# RingBoard.net
KiCad netlist of a schematic drawn in EAGLE
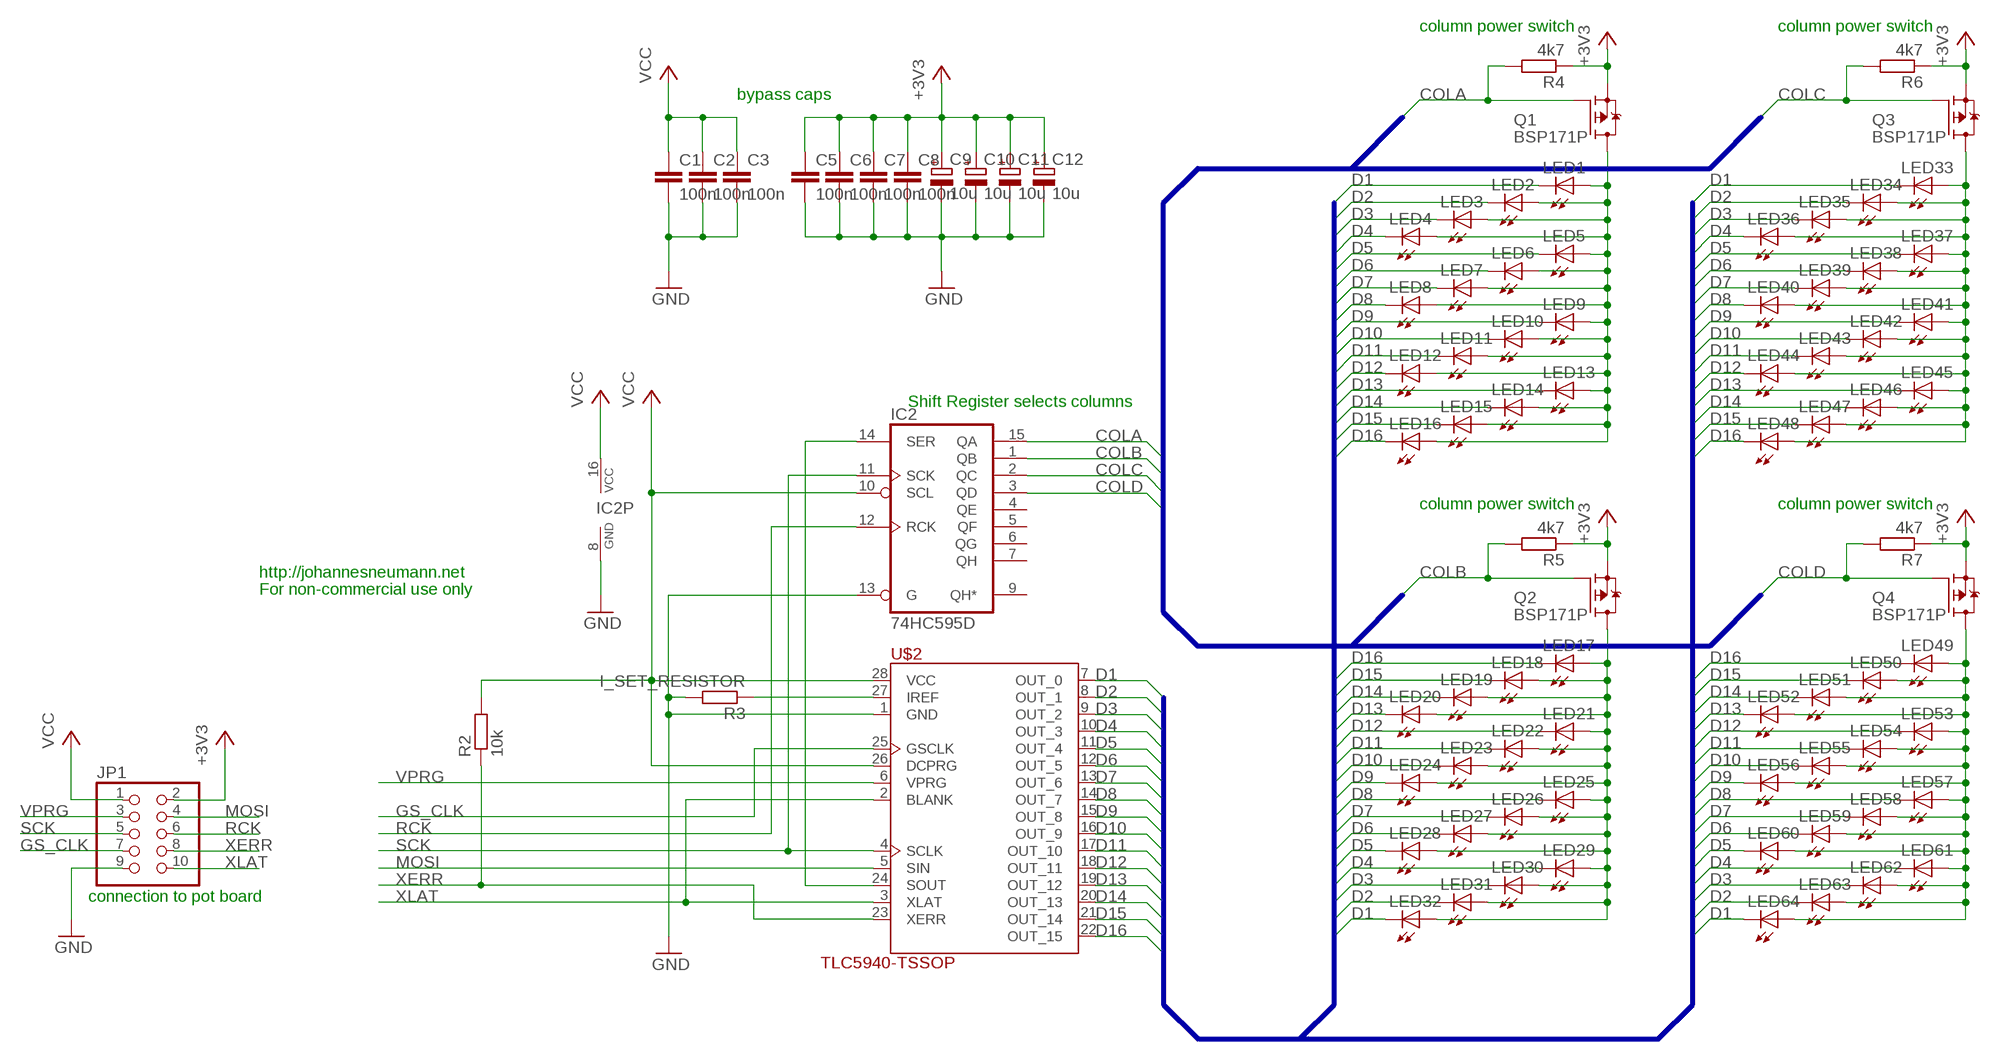
[diagram p0: schematic, sheet 1]

(export (version "E")
  (design (tool "Eeschema 10.0.6"))
  (components
    (comp (ref "C1")
      (value "100n")
      (footprint "eagle-import:C0603")
      (libsource (lib "eagle-import") (part "C-EUC0603"))
    )
    (comp (ref "C2")
      (value "100n")
      (footprint "eagle-import:C0603")
      (libsource (lib "eagle-import") (part "C-EUC0603"))
    )
    (comp (ref "C3")
      (value "100n")
      (footprint "eagle-import:C0603")
      (libsource (lib "eagle-import") (part "C-EUC0603"))
    )
    (comp (ref "C5")
      (value "100n")
      (footprint "eagle-import:C0603")
      (libsource (lib "eagle-import") (part "C-EUC0603"))
    )
    (comp (ref "C6")
      (value "100n")
      (footprint "eagle-import:C0603")
      (libsource (lib "eagle-import") (part "C-EUC0603"))
    )
    (comp (ref "C7")
      (value "100n")
      (footprint "eagle-import:C0603")
      (libsource (lib "eagle-import") (part "C-EUC0603"))
    )
    (comp (ref "C8")
      (value "100n")
      (footprint "eagle-import:C0603")
      (libsource (lib "eagle-import") (part "C-EUC0603"))
    )
    (comp (ref "C9")
      (value "10u")
      (footprint "eagle-import:153CLV-0605")
      (libsource (lib "eagle-import") (part "CPOL-EU153CLV-0605"))
    )
    (comp (ref "C10")
      (value "10u")
      (footprint "eagle-import:153CLV-0605")
      (libsource (lib "eagle-import") (part "CPOL-EU153CLV-0605"))
    )
    (comp (ref "C11")
      (value "10u")
      (footprint "eagle-import:153CLV-0605")
      (libsource (lib "eagle-import") (part "CPOL-EU153CLV-0605"))
    )
    (comp (ref "C12")
      (value "10u")
      (footprint "eagle-import:153CLV-0605")
      (libsource (lib "eagle-import") (part "CPOL-EU153CLV-0605"))
    )
    (comp (ref "IC2")
      (value "74HC595D")
      (footprint "eagle-import:SO16")
      (libsource (lib "eagle-import") (part "74595DHC"))
    )
    (comp (ref "JP1")
      (value "PINHD-2X5_2.54-SMD")
      (footprint "eagle-import:2X05SMD")
      (libsource (lib "eagle-import") (part "PINHD-2X5_2.54-SMD"))
    )
    (comp (ref "LED1")
      (value "LEDCHIP-LED0805")
      (footprint "eagle-import:CHIP-LED0805")
      (libsource (lib "eagle-import") (part "LEDCHIP-LED0805"))
    )
    (comp (ref "LED2")
      (value "LEDCHIP-LED0805")
      (footprint "eagle-import:CHIP-LED0805")
      (libsource (lib "eagle-import") (part "LEDCHIP-LED0805"))
    )
    (comp (ref "LED3")
      (value "LEDCHIP-LED0805")
      (footprint "eagle-import:CHIP-LED0805")
      (libsource (lib "eagle-import") (part "LEDCHIP-LED0805"))
    )
    (comp (ref "LED4")
      (value "LEDCHIP-LED0805")
      (footprint "eagle-import:CHIP-LED0805")
      (libsource (lib "eagle-import") (part "LEDCHIP-LED0805"))
    )
    (comp (ref "LED5")
      (value "LEDCHIP-LED0805")
      (footprint "eagle-import:CHIP-LED0805")
      (libsource (lib "eagle-import") (part "LEDCHIP-LED0805"))
    )
    (comp (ref "LED6")
      (value "LEDCHIP-LED0805")
      (footprint "eagle-import:CHIP-LED0805")
      (libsource (lib "eagle-import") (part "LEDCHIP-LED0805"))
    )
    (comp (ref "LED7")
      (value "LEDCHIP-LED0805")
      (footprint "eagle-import:CHIP-LED0805")
      (libsource (lib "eagle-import") (part "LEDCHIP-LED0805"))
    )
    (comp (ref "LED8")
      (value "LEDCHIP-LED0805")
      (footprint "eagle-import:CHIP-LED0805")
      (libsource (lib "eagle-import") (part "LEDCHIP-LED0805"))
    )
    (comp (ref "LED9")
      (value "LEDCHIP-LED0805")
      (footprint "eagle-import:CHIP-LED0805")
      (libsource (lib "eagle-import") (part "LEDCHIP-LED0805"))
    )
    (comp (ref "LED10")
      (value "LEDCHIP-LED0805")
      (footprint "eagle-import:CHIP-LED0805")
      (libsource (lib "eagle-import") (part "LEDCHIP-LED0805"))
    )
    (comp (ref "LED11")
      (value "LEDCHIP-LED0805")
      (footprint "eagle-import:CHIP-LED0805")
      (libsource (lib "eagle-import") (part "LEDCHIP-LED0805"))
    )
    (comp (ref "LED12")
      (value "LEDCHIP-LED0805")
      (footprint "eagle-import:CHIP-LED0805")
      (libsource (lib "eagle-import") (part "LEDCHIP-LED0805"))
    )
    (comp (ref "LED13")
      (value "LEDCHIP-LED0805")
      (footprint "eagle-import:CHIP-LED0805")
      (libsource (lib "eagle-import") (part "LEDCHIP-LED0805"))
    )
    (comp (ref "LED14")
      (value "LEDCHIP-LED0805")
      (footprint "eagle-import:CHIP-LED0805")
      (libsource (lib "eagle-import") (part "LEDCHIP-LED0805"))
    )
    (comp (ref "LED15")
      (value "LEDCHIP-LED0805")
      (footprint "eagle-import:CHIP-LED0805")
      (libsource (lib "eagle-import") (part "LEDCHIP-LED0805"))
    )
    (comp (ref "LED16")
      (value "LEDCHIP-LED0805")
      (footprint "eagle-import:CHIP-LED0805")
      (libsource (lib "eagle-import") (part "LEDCHIP-LED0805"))
    )
    (comp (ref "LED17")
      (value "LEDCHIP-LED0805")
      (footprint "eagle-import:CHIP-LED0805")
      (libsource (lib "eagle-import") (part "LEDCHIP-LED0805"))
    )
    (comp (ref "LED18")
      (value "LEDCHIP-LED0805")
      (footprint "eagle-import:CHIP-LED0805")
      (libsource (lib "eagle-import") (part "LEDCHIP-LED0805"))
    )
    (comp (ref "LED19")
      (value "LEDCHIP-LED0805")
      (footprint "eagle-import:CHIP-LED0805")
      (libsource (lib "eagle-import") (part "LEDCHIP-LED0805"))
    )
    (comp (ref "LED20")
      (value "LEDCHIP-LED0805")
      (footprint "eagle-import:CHIP-LED0805")
      (libsource (lib "eagle-import") (part "LEDCHIP-LED0805"))
    )
    (comp (ref "LED21")
      (value "LEDCHIP-LED0805")
      (footprint "eagle-import:CHIP-LED0805")
      (libsource (lib "eagle-import") (part "LEDCHIP-LED0805"))
    )
    (comp (ref "LED22")
      (value "LEDCHIP-LED0805")
      (footprint "eagle-import:CHIP-LED0805")
      (libsource (lib "eagle-import") (part "LEDCHIP-LED0805"))
    )
    (comp (ref "LED23")
      (value "LEDCHIP-LED0805")
      (footprint "eagle-import:CHIP-LED0805")
      (libsource (lib "eagle-import") (part "LEDCHIP-LED0805"))
    )
    (comp (ref "LED24")
      (value "LEDCHIP-LED0805")
      (footprint "eagle-import:CHIP-LED0805")
      (libsource (lib "eagle-import") (part "LEDCHIP-LED0805"))
    )
    (comp (ref "LED25")
      (value "LEDCHIP-LED0805")
      (footprint "eagle-import:CHIP-LED0805")
      (libsource (lib "eagle-import") (part "LEDCHIP-LED0805"))
    )
    (comp (ref "LED26")
      (value "LEDCHIP-LED0805")
      (footprint "eagle-import:CHIP-LED0805")
      (libsource (lib "eagle-import") (part "LEDCHIP-LED0805"))
    )
    (comp (ref "LED27")
      (value "LEDCHIP-LED0805")
      (footprint "eagle-import:CHIP-LED0805")
      (libsource (lib "eagle-import") (part "LEDCHIP-LED0805"))
    )
    (comp (ref "LED28")
      (value "LEDCHIP-LED0805")
      (footprint "eagle-import:CHIP-LED0805")
      (libsource (lib "eagle-import") (part "LEDCHIP-LED0805"))
    )
    (comp (ref "LED29")
      (value "LEDCHIP-LED0805")
      (footprint "eagle-import:CHIP-LED0805")
      (libsource (lib "eagle-import") (part "LEDCHIP-LED0805"))
    )
    (comp (ref "LED30")
      (value "LEDCHIP-LED0805")
      (footprint "eagle-import:CHIP-LED0805")
      (libsource (lib "eagle-import") (part "LEDCHIP-LED0805"))
    )
    (comp (ref "LED31")
      (value "LEDCHIP-LED0805")
      (footprint "eagle-import:CHIP-LED0805")
      (libsource (lib "eagle-import") (part "LEDCHIP-LED0805"))
    )
    (comp (ref "LED32")
      (value "LEDCHIP-LED0805")
      (footprint "eagle-import:CHIP-LED0805")
      (libsource (lib "eagle-import") (part "LEDCHIP-LED0805"))
    )
    (comp (ref "LED33")
      (value "LEDCHIP-LED0805")
      (footprint "eagle-import:CHIP-LED0805")
      (libsource (lib "eagle-import") (part "LEDCHIP-LED0805"))
    )
    (comp (ref "LED34")
      (value "LEDCHIP-LED0805")
      (footprint "eagle-import:CHIP-LED0805")
      (libsource (lib "eagle-import") (part "LEDCHIP-LED0805"))
    )
    (comp (ref "LED35")
      (value "LEDCHIP-LED0805")
      (footprint "eagle-import:CHIP-LED0805")
      (libsource (lib "eagle-import") (part "LEDCHIP-LED0805"))
    )
    (comp (ref "LED36")
      (value "LEDCHIP-LED0805")
      (footprint "eagle-import:CHIP-LED0805")
      (libsource (lib "eagle-import") (part "LEDCHIP-LED0805"))
    )
    (comp (ref "LED37")
      (value "LEDCHIP-LED0805")
      (footprint "eagle-import:CHIP-LED0805")
      (libsource (lib "eagle-import") (part "LEDCHIP-LED0805"))
    )
    (comp (ref "LED38")
      (value "LEDCHIP-LED0805")
      (footprint "eagle-import:CHIP-LED0805")
      (libsource (lib "eagle-import") (part "LEDCHIP-LED0805"))
    )
    (comp (ref "LED39")
      (value "LEDCHIP-LED0805")
      (footprint "eagle-import:CHIP-LED0805")
      (libsource (lib "eagle-import") (part "LEDCHIP-LED0805"))
    )
    (comp (ref "LED40")
      (value "LEDCHIP-LED0805")
      (footprint "eagle-import:CHIP-LED0805")
      (libsource (lib "eagle-import") (part "LEDCHIP-LED0805"))
    )
    (comp (ref "LED41")
      (value "LEDCHIP-LED0805")
      (footprint "eagle-import:CHIP-LED0805")
      (libsource (lib "eagle-import") (part "LEDCHIP-LED0805"))
    )
    (comp (ref "LED42")
      (value "LEDCHIP-LED0805")
      (footprint "eagle-import:CHIP-LED0805")
      (libsource (lib "eagle-import") (part "LEDCHIP-LED0805"))
    )
    (comp (ref "LED43")
      (value "LEDCHIP-LED0805")
      (footprint "eagle-import:CHIP-LED0805")
      (libsource (lib "eagle-import") (part "LEDCHIP-LED0805"))
    )
    (comp (ref "LED44")
      (value "LEDCHIP-LED0805")
      (footprint "eagle-import:CHIP-LED0805")
      (libsource (lib "eagle-import") (part "LEDCHIP-LED0805"))
    )
    (comp (ref "LED45")
      (value "LEDCHIP-LED0805")
      (footprint "eagle-import:CHIP-LED0805")
      (libsource (lib "eagle-import") (part "LEDCHIP-LED0805"))
    )
    (comp (ref "LED46")
      (value "LEDCHIP-LED0805")
      (footprint "eagle-import:CHIP-LED0805")
      (libsource (lib "eagle-import") (part "LEDCHIP-LED0805"))
    )
    (comp (ref "LED47")
      (value "LEDCHIP-LED0805")
      (footprint "eagle-import:CHIP-LED0805")
      (libsource (lib "eagle-import") (part "LEDCHIP-LED0805"))
    )
    (comp (ref "LED48")
      (value "LEDCHIP-LED0805")
      (footprint "eagle-import:CHIP-LED0805")
      (libsource (lib "eagle-import") (part "LEDCHIP-LED0805"))
    )
    (comp (ref "LED49")
      (value "LEDCHIP-LED0805")
      (footprint "eagle-import:CHIP-LED0805")
      (libsource (lib "eagle-import") (part "LEDCHIP-LED0805"))
    )
    (comp (ref "LED50")
      (value "LEDCHIP-LED0805")
      (footprint "eagle-import:CHIP-LED0805")
      (libsource (lib "eagle-import") (part "LEDCHIP-LED0805"))
    )
    (comp (ref "LED51")
      (value "LEDCHIP-LED0805")
      (footprint "eagle-import:CHIP-LED0805")
      (libsource (lib "eagle-import") (part "LEDCHIP-LED0805"))
    )
    (comp (ref "LED52")
      (value "LEDCHIP-LED0805")
      (footprint "eagle-import:CHIP-LED0805")
      (libsource (lib "eagle-import") (part "LEDCHIP-LED0805"))
    )
    (comp (ref "LED53")
      (value "LEDCHIP-LED0805")
      (footprint "eagle-import:CHIP-LED0805")
      (libsource (lib "eagle-import") (part "LEDCHIP-LED0805"))
    )
    (comp (ref "LED54")
      (value "LEDCHIP-LED0805")
      (footprint "eagle-import:CHIP-LED0805")
      (libsource (lib "eagle-import") (part "LEDCHIP-LED0805"))
    )
    (comp (ref "LED55")
      (value "LEDCHIP-LED0805")
      (footprint "eagle-import:CHIP-LED0805")
      (libsource (lib "eagle-import") (part "LEDCHIP-LED0805"))
    )
    (comp (ref "LED56")
      (value "LEDCHIP-LED0805")
      (footprint "eagle-import:CHIP-LED0805")
      (libsource (lib "eagle-import") (part "LEDCHIP-LED0805"))
    )
    (comp (ref "LED57")
      (value "LEDCHIP-LED0805")
      (footprint "eagle-import:CHIP-LED0805")
      (libsource (lib "eagle-import") (part "LEDCHIP-LED0805"))
    )
    (comp (ref "LED58")
      (value "LEDCHIP-LED0805")
      (footprint "eagle-import:CHIP-LED0805")
      (libsource (lib "eagle-import") (part "LEDCHIP-LED0805"))
    )
    (comp (ref "LED59")
      (value "LEDCHIP-LED0805")
      (footprint "eagle-import:CHIP-LED0805")
      (libsource (lib "eagle-import") (part "LEDCHIP-LED0805"))
    )
    (comp (ref "LED60")
      (value "LEDCHIP-LED0805")
      (footprint "eagle-import:CHIP-LED0805")
      (libsource (lib "eagle-import") (part "LEDCHIP-LED0805"))
    )
    (comp (ref "LED61")
      (value "LEDCHIP-LED0805")
      (footprint "eagle-import:CHIP-LED0805")
      (libsource (lib "eagle-import") (part "LEDCHIP-LED0805"))
    )
    (comp (ref "LED62")
      (value "LEDCHIP-LED0805")
      (footprint "eagle-import:CHIP-LED0805")
      (libsource (lib "eagle-import") (part "LEDCHIP-LED0805"))
    )
    (comp (ref "LED63")
      (value "LEDCHIP-LED0805")
      (footprint "eagle-import:CHIP-LED0805")
      (libsource (lib "eagle-import") (part "LEDCHIP-LED0805"))
    )
    (comp (ref "LED64")
      (value "LEDCHIP-LED0805")
      (footprint "eagle-import:CHIP-LED0805")
      (libsource (lib "eagle-import") (part "LEDCHIP-LED0805"))
    )
    (comp (ref "Q1")
      (value "BSP171P")
      (footprint "eagle-import:SOT223")
      (libsource (lib "eagle-import") (part "BSP170P"))
    )
    (comp (ref "Q2")
      (value "BSP171P")
      (footprint "eagle-import:SOT223")
      (libsource (lib "eagle-import") (part "BSP170P"))
    )
    (comp (ref "Q3")
      (value "BSP171P")
      (footprint "eagle-import:SOT223")
      (libsource (lib "eagle-import") (part "BSP170P"))
    )
    (comp (ref "Q4")
      (value "BSP171P")
      (footprint "eagle-import:SOT223")
      (libsource (lib "eagle-import") (part "BSP170P"))
    )
    (comp (ref "R2")
      (value "10k")
      (footprint "eagle-import:R0603")
      (libsource (lib "eagle-import") (part "R-EU_R0603"))
    )
    (comp (ref "R3")
      (value "I_SET_RESISTOR")
      (footprint "eagle-import:M1406")
      (libsource (lib "eagle-import") (part "R-EU_M1406"))
    )
    (comp (ref "R4")
      (value "4k7")
      (footprint "eagle-import:R0603")
      (libsource (lib "eagle-import") (part "R-EU_R0603"))
    )
    (comp (ref "R5")
      (value "4k7")
      (footprint "eagle-import:R0603")
      (libsource (lib "eagle-import") (part "R-EU_R0603"))
    )
    (comp (ref "R6")
      (value "4k7")
      (footprint "eagle-import:R0603")
      (libsource (lib "eagle-import") (part "R-EU_R0603"))
    )
    (comp (ref "R7")
      (value "4k7")
      (footprint "eagle-import:R0603")
      (libsource (lib "eagle-import") (part "R-EU_R0603"))
    )
    (comp (ref "U$2")
      (value "TLC5940-TSSOP")
      (footprint "eagle-import:HTSSOP-28")
      (libsource (lib "eagle-import") (part "TLC5940-TSSOP"))
    )
  )
  (nets
    (net (code "1") (name "+3V3") (class "Default")
      (node (ref "C10") (pin "+") (pinfunction "+_+") (pintype "passive"))
      (node (ref "C11") (pin "+") (pinfunction "+_+") (pintype "passive"))
      (node (ref "C12") (pin "+") (pinfunction "+_+") (pintype "passive"))
      (node (ref "C5") (pin "1") (pinfunction "1_1") (pintype "passive"))
      (node (ref "C6") (pin "1") (pinfunction "1_1") (pintype "passive"))
      (node (ref "C7") (pin "1") (pinfunction "1_1") (pintype "passive"))
      (node (ref "C8") (pin "1") (pinfunction "1_1") (pintype "passive"))
      (node (ref "C9") (pin "+") (pinfunction "+_+") (pintype "passive"))
      (node (ref "JP1") (pin "2") (pinfunction "2_2") (pintype "passive"))
      (node (ref "Q1") (pin "3") (pinfunction "S_3") (pintype "passive"))
      (node (ref "Q2") (pin "3") (pinfunction "S_3") (pintype "passive"))
      (node (ref "Q3") (pin "3") (pinfunction "S_3") (pintype "passive"))
      (node (ref "Q4") (pin "3") (pinfunction "S_3") (pintype "passive"))
      (node (ref "R4") (pin "1") (pinfunction "1_1") (pintype "passive"))
      (node (ref "R5") (pin "1") (pinfunction "1_1") (pintype "passive"))
      (node (ref "R6") (pin "1") (pinfunction "1_1") (pintype "passive"))
      (node (ref "R7") (pin "1") (pinfunction "1_1") (pintype "passive"))
    )
    (net (code "2") (name "/COLA") (class "Default")
      (node (ref "IC2") (pin "15") (pinfunction "QA_15") (pintype "tri_state"))
      (node (ref "Q1") (pin "1") (pinfunction "G_1") (pintype "passive"))
      (node (ref "R4") (pin "2") (pinfunction "2_2") (pintype "passive"))
    )
    (net (code "3") (name "/COLB") (class "Default")
      (node (ref "IC2") (pin "1") (pinfunction "QB_1") (pintype "tri_state"))
      (node (ref "Q2") (pin "1") (pinfunction "G_1") (pintype "passive"))
      (node (ref "R5") (pin "2") (pinfunction "2_2") (pintype "passive"))
    )
    (net (code "4") (name "/COLC") (class "Default")
      (node (ref "IC2") (pin "2") (pinfunction "QC_2") (pintype "tri_state"))
      (node (ref "Q3") (pin "1") (pinfunction "G_1") (pintype "passive"))
      (node (ref "R6") (pin "2") (pinfunction "2_2") (pintype "passive"))
    )
    (net (code "5") (name "/COLD") (class "Default")
      (node (ref "IC2") (pin "3") (pinfunction "QD_3") (pintype "tri_state"))
      (node (ref "Q4") (pin "1") (pinfunction "G_1") (pintype "passive"))
      (node (ref "R7") (pin "2") (pinfunction "2_2") (pintype "passive"))
    )
    (net (code "6") (name "/D1") (class "Default")
      (node (ref "LED1") (pin "C") (pinfunction "C_C") (pintype "passive"))
      (node (ref "LED32") (pin "C") (pinfunction "C_C") (pintype "passive"))
      (node (ref "LED33") (pin "C") (pinfunction "C_C") (pintype "passive"))
      (node (ref "LED64") (pin "C") (pinfunction "C_C") (pintype "passive"))
      (node (ref "U$2") (pin "7") (pinfunction "OUT_0_7") (pintype "output"))
    )
    (net (code "7") (name "/D2") (class "Default")
      (node (ref "LED2") (pin "C") (pinfunction "C_C") (pintype "passive"))
      (node (ref "LED31") (pin "C") (pinfunction "C_C") (pintype "passive"))
      (node (ref "LED34") (pin "C") (pinfunction "C_C") (pintype "passive"))
      (node (ref "LED63") (pin "C") (pinfunction "C_C") (pintype "passive"))
      (node (ref "U$2") (pin "8") (pinfunction "OUT_1_8") (pintype "output"))
    )
    (net (code "8") (name "/D3") (class "Default")
      (node (ref "LED3") (pin "C") (pinfunction "C_C") (pintype "passive"))
      (node (ref "LED30") (pin "C") (pinfunction "C_C") (pintype "passive"))
      (node (ref "LED35") (pin "C") (pinfunction "C_C") (pintype "passive"))
      (node (ref "LED62") (pin "C") (pinfunction "C_C") (pintype "passive"))
      (node (ref "U$2") (pin "9") (pinfunction "OUT_2_9") (pintype "output"))
    )
    (net (code "9") (name "/D4") (class "Default")
      (node (ref "LED29") (pin "C") (pinfunction "C_C") (pintype "passive"))
      (node (ref "LED36") (pin "C") (pinfunction "C_C") (pintype "passive"))
      (node (ref "LED4") (pin "C") (pinfunction "C_C") (pintype "passive"))
      (node (ref "LED61") (pin "C") (pinfunction "C_C") (pintype "passive"))
      (node (ref "U$2") (pin "10") (pinfunction "OUT_3_10") (pintype "output"))
    )
    (net (code "10") (name "/D5") (class "Default")
      (node (ref "LED28") (pin "C") (pinfunction "C_C") (pintype "passive"))
      (node (ref "LED37") (pin "C") (pinfunction "C_C") (pintype "passive"))
      (node (ref "LED5") (pin "C") (pinfunction "C_C") (pintype "passive"))
      (node (ref "LED60") (pin "C") (pinfunction "C_C") (pintype "passive"))
      (node (ref "U$2") (pin "11") (pinfunction "OUT_4_11") (pintype "output"))
    )
    (net (code "11") (name "/D6") (class "Default")
      (node (ref "LED27") (pin "C") (pinfunction "C_C") (pintype "passive"))
      (node (ref "LED38") (pin "C") (pinfunction "C_C") (pintype "passive"))
      (node (ref "LED59") (pin "C") (pinfunction "C_C") (pintype "passive"))
      (node (ref "LED6") (pin "C") (pinfunction "C_C") (pintype "passive"))
      (node (ref "U$2") (pin "12") (pinfunction "OUT_5_12") (pintype "output"))
    )
    (net (code "12") (name "/D7") (class "Default")
      (node (ref "LED26") (pin "C") (pinfunction "C_C") (pintype "passive"))
      (node (ref "LED39") (pin "C") (pinfunction "C_C") (pintype "passive"))
      (node (ref "LED58") (pin "C") (pinfunction "C_C") (pintype "passive"))
      (node (ref "LED7") (pin "C") (pinfunction "C_C") (pintype "passive"))
      (node (ref "U$2") (pin "13") (pinfunction "OUT_6_13") (pintype "output"))
    )
    (net (code "13") (name "/D8") (class "Default")
      (node (ref "LED25") (pin "C") (pinfunction "C_C") (pintype "passive"))
      (node (ref "LED40") (pin "C") (pinfunction "C_C") (pintype "passive"))
      (node (ref "LED57") (pin "C") (pinfunction "C_C") (pintype "passive"))
      (node (ref "LED8") (pin "C") (pinfunction "C_C") (pintype "passive"))
      (node (ref "U$2") (pin "14") (pinfunction "OUT_7_14") (pintype "output"))
    )
    (net (code "14") (name "/D9") (class "Default")
      (node (ref "LED24") (pin "C") (pinfunction "C_C") (pintype "passive"))
      (node (ref "LED41") (pin "C") (pinfunction "C_C") (pintype "passive"))
      (node (ref "LED56") (pin "C") (pinfunction "C_C") (pintype "passive"))
      (node (ref "LED9") (pin "C") (pinfunction "C_C") (pintype "passive"))
      (node (ref "U$2") (pin "15") (pinfunction "OUT_8_15") (pintype "output"))
    )
    (net (code "15") (name "/D10") (class "Default")
      (node (ref "LED10") (pin "C") (pinfunction "C_C") (pintype "passive"))
      (node (ref "LED23") (pin "C") (pinfunction "C_C") (pintype "passive"))
      (node (ref "LED42") (pin "C") (pinfunction "C_C") (pintype "passive"))
      (node (ref "LED55") (pin "C") (pinfunction "C_C") (pintype "passive"))
      (node (ref "U$2") (pin "16") (pinfunction "OUT_9_16") (pintype "output"))
    )
    (net (code "16") (name "/D11") (class "Default")
      (node (ref "LED11") (pin "C") (pinfunction "C_C") (pintype "passive"))
      (node (ref "LED22") (pin "C") (pinfunction "C_C") (pintype "passive"))
      (node (ref "LED43") (pin "C") (pinfunction "C_C") (pintype "passive"))
      (node (ref "LED54") (pin "C") (pinfunction "C_C") (pintype "passive"))
      (node (ref "U$2") (pin "17") (pinfunction "OUT_10_17") (pintype "output"))
    )
    (net (code "17") (name "/D12") (class "Default")
      (node (ref "LED12") (pin "C") (pinfunction "C_C") (pintype "passive"))
      (node (ref "LED21") (pin "C") (pinfunction "C_C") (pintype "passive"))
      (node (ref "LED44") (pin "C") (pinfunction "C_C") (pintype "passive"))
      (node (ref "LED53") (pin "C") (pinfunction "C_C") (pintype "passive"))
      (node (ref "U$2") (pin "18") (pinfunction "OUT_11_18") (pintype "output"))
    )
    (net (code "18") (name "/D13") (class "Default")
      (node (ref "LED13") (pin "C") (pinfunction "C_C") (pintype "passive"))
      (node (ref "LED20") (pin "C") (pinfunction "C_C") (pintype "passive"))
      (node (ref "LED45") (pin "C") (pinfunction "C_C") (pintype "passive"))
      (node (ref "LED52") (pin "C") (pinfunction "C_C") (pintype "passive"))
      (node (ref "U$2") (pin "19") (pinfunction "OUT_12_19") (pintype "output"))
    )
    (net (code "19") (name "/D14") (class "Default")
      (node (ref "LED14") (pin "C") (pinfunction "C_C") (pintype "passive"))
      (node (ref "LED19") (pin "C") (pinfunction "C_C") (pintype "passive"))
      (node (ref "LED46") (pin "C") (pinfunction "C_C") (pintype "passive"))
      (node (ref "LED51") (pin "C") (pinfunction "C_C") (pintype "passive"))
      (node (ref "U$2") (pin "20") (pinfunction "OUT_13_20") (pintype "output"))
    )
    (net (code "20") (name "/D15") (class "Default")
      (node (ref "LED15") (pin "C") (pinfunction "C_C") (pintype "passive"))
      (node (ref "LED18") (pin "C") (pinfunction "C_C") (pintype "passive"))
      (node (ref "LED47") (pin "C") (pinfunction "C_C") (pintype "passive"))
      (node (ref "LED50") (pin "C") (pinfunction "C_C") (pintype "passive"))
      (node (ref "U$2") (pin "21") (pinfunction "OUT_14_21") (pintype "output"))
    )
    (net (code "21") (name "/D16") (class "Default")
      (node (ref "LED16") (pin "C") (pinfunction "C_C") (pintype "passive"))
      (node (ref "LED17") (pin "C") (pinfunction "C_C") (pintype "passive"))
      (node (ref "LED48") (pin "C") (pinfunction "C_C") (pintype "passive"))
      (node (ref "LED49") (pin "C") (pinfunction "C_C") (pintype "passive"))
      (node (ref "U$2") (pin "22") (pinfunction "OUT_15_22") (pintype "output"))
    )
    (net (code "22") (name "/GS_CLK") (class "Default")
      (node (ref "JP1") (pin "7") (pinfunction "7_7") (pintype "passive"))
      (node (ref "U$2") (pin "25") (pinfunction "GSCLK_25") (pintype "input"))
    )
    (net (code "23") (name "/MOSI") (class "Default")
      (node (ref "JP1") (pin "4") (pinfunction "4_4") (pintype "passive"))
      (node (ref "U$2") (pin "5") (pinfunction "SIN_5") (pintype "input"))
    )
    (net (code "24") (name "/RCK") (class "Default")
      (node (ref "IC2") (pin "12") (pinfunction "RCK_12") (pintype "input"))
      (node (ref "JP1") (pin "6") (pinfunction "6_6") (pintype "passive"))
    )
    (net (code "25") (name "/SCK") (class "Default")
      (node (ref "IC2") (pin "11") (pinfunction "SCK_11") (pintype "input"))
      (node (ref "JP1") (pin "5") (pinfunction "5_5") (pintype "passive"))
      (node (ref "U$2") (pin "4") (pinfunction "SCLK_4") (pintype "input"))
    )
    (net (code "26") (name "/VPRG") (class "Default")
      (node (ref "JP1") (pin "3") (pinfunction "3_3") (pintype "passive"))
      (node (ref "U$2") (pin "6") (pinfunction "VPRG_6") (pintype "input"))
    )
    (net (code "27") (name "/XERR") (class "Default")
      (node (ref "JP1") (pin "8") (pinfunction "8_8") (pintype "passive"))
      (node (ref "R2") (pin "1") (pinfunction "1_1") (pintype "passive"))
      (node (ref "U$2") (pin "23") (pinfunction "XERR_23") (pintype "output"))
    )
    (net (code "28") (name "/XLAT") (class "Default")
      (node (ref "JP1") (pin "10") (pinfunction "10_10") (pintype "passive"))
      (node (ref "U$2") (pin "2") (pinfunction "BLANK_2") (pintype "input"))
      (node (ref "U$2") (pin "3") (pinfunction "XLAT_3") (pintype "input"))
    )
    (net (code "29") (name "GND") (class "Default")
      (node (ref "C1") (pin "2") (pinfunction "2_2") (pintype "passive"))
      (node (ref "C10") (pin "-") (pinfunction "-_-") (pintype "passive"))
      (node (ref "C11") (pin "-") (pinfunction "-_-") (pintype "passive"))
      (node (ref "C12") (pin "-") (pinfunction "-_-") (pintype "passive"))
      (node (ref "C2") (pin "2") (pinfunction "2_2") (pintype "passive"))
      (node (ref "C3") (pin "2") (pinfunction "2_2") (pintype "passive"))
      (node (ref "C5") (pin "2") (pinfunction "2_2") (pintype "passive"))
      (node (ref "C6") (pin "2") (pinfunction "2_2") (pintype "passive"))
      (node (ref "C7") (pin "2") (pinfunction "2_2") (pintype "passive"))
      (node (ref "C8") (pin "2") (pinfunction "2_2") (pintype "passive"))
      (node (ref "C9") (pin "-") (pinfunction "-_-") (pintype "passive"))
      (node (ref "IC2") (pin "13") (pinfunction "G_13") (pintype "input"))
      (node (ref "IC2") (pin "8") (pinfunction "GND_8") (pintype "power_in"))
      (node (ref "JP1") (pin "9") (pinfunction "9_9") (pintype "passive"))
      (node (ref "R3") (pin "2") (pinfunction "2_2") (pintype "passive"))
      (node (ref "U$2") (pin "1") (pinfunction "GND_1") (pintype "power_in"))
    )
    (net (code "30") (name "Net-(IC2A-SER)") (class "Default")
      (node (ref "IC2") (pin "14") (pinfunction "SER_14") (pintype "input"))
      (node (ref "U$2") (pin "24") (pinfunction "SOUT_24") (pintype "output"))
    )
    (net (code "31") (name "Net-(LED1-PadA)") (class "Default")
      (node (ref "LED1") (pin "A") (pinfunction "A_A") (pintype "passive"))
      (node (ref "LED10") (pin "A") (pinfunction "A_A") (pintype "passive"))
      (node (ref "LED11") (pin "A") (pinfunction "A_A") (pintype "passive"))
      (node (ref "LED12") (pin "A") (pinfunction "A_A") (pintype "passive"))
      (node (ref "LED13") (pin "A") (pinfunction "A_A") (pintype "passive"))
      (node (ref "LED14") (pin "A") (pinfunction "A_A") (pintype "passive"))
      (node (ref "LED15") (pin "A") (pinfunction "A_A") (pintype "passive"))
      (node (ref "LED16") (pin "A") (pinfunction "A_A") (pintype "passive"))
      (node (ref "LED2") (pin "A") (pinfunction "A_A") (pintype "passive"))
      (node (ref "LED3") (pin "A") (pinfunction "A_A") (pintype "passive"))
      (node (ref "LED4") (pin "A") (pinfunction "A_A") (pintype "passive"))
      (node (ref "LED5") (pin "A") (pinfunction "A_A") (pintype "passive"))
      (node (ref "LED6") (pin "A") (pinfunction "A_A") (pintype "passive"))
      (node (ref "LED7") (pin "A") (pinfunction "A_A") (pintype "passive"))
      (node (ref "LED8") (pin "A") (pinfunction "A_A") (pintype "passive"))
      (node (ref "LED9") (pin "A") (pinfunction "A_A") (pintype "passive"))
      (node (ref "Q1") (pin "2") (pinfunction "D_2") (pintype "passive"))
      (node (ref "Q1") (pin "4") (pinfunction "D_4") (pintype "passive"))
    )
    (net (code "32") (name "Net-(LED17-PadA)") (class "Default")
      (node (ref "LED17") (pin "A") (pinfunction "A_A") (pintype "passive"))
      (node (ref "LED18") (pin "A") (pinfunction "A_A") (pintype "passive"))
      (node (ref "LED19") (pin "A") (pinfunction "A_A") (pintype "passive"))
      (node (ref "LED20") (pin "A") (pinfunction "A_A") (pintype "passive"))
      (node (ref "LED21") (pin "A") (pinfunction "A_A") (pintype "passive"))
      (node (ref "LED22") (pin "A") (pinfunction "A_A") (pintype "passive"))
      (node (ref "LED23") (pin "A") (pinfunction "A_A") (pintype "passive"))
      (node (ref "LED24") (pin "A") (pinfunction "A_A") (pintype "passive"))
      (node (ref "LED25") (pin "A") (pinfunction "A_A") (pintype "passive"))
      (node (ref "LED26") (pin "A") (pinfunction "A_A") (pintype "passive"))
      (node (ref "LED27") (pin "A") (pinfunction "A_A") (pintype "passive"))
      (node (ref "LED28") (pin "A") (pinfunction "A_A") (pintype "passive"))
      (node (ref "LED29") (pin "A") (pinfunction "A_A") (pintype "passive"))
      (node (ref "LED30") (pin "A") (pinfunction "A_A") (pintype "passive"))
      (node (ref "LED31") (pin "A") (pinfunction "A_A") (pintype "passive"))
      (node (ref "LED32") (pin "A") (pinfunction "A_A") (pintype "passive"))
      (node (ref "Q2") (pin "2") (pinfunction "D_2") (pintype "passive"))
      (node (ref "Q2") (pin "4") (pinfunction "D_4") (pintype "passive"))
    )
    (net (code "33") (name "Net-(LED33-PadA)") (class "Default")
      (node (ref "LED33") (pin "A") (pinfunction "A_A") (pintype "passive"))
      (node (ref "LED34") (pin "A") (pinfunction "A_A") (pintype "passive"))
      (node (ref "LED35") (pin "A") (pinfunction "A_A") (pintype "passive"))
      (node (ref "LED36") (pin "A") (pinfunction "A_A") (pintype "passive"))
      (node (ref "LED37") (pin "A") (pinfunction "A_A") (pintype "passive"))
      (node (ref "LED38") (pin "A") (pinfunction "A_A") (pintype "passive"))
      (node (ref "LED39") (pin "A") (pinfunction "A_A") (pintype "passive"))
      (node (ref "LED40") (pin "A") (pinfunction "A_A") (pintype "passive"))
      (node (ref "LED41") (pin "A") (pinfunction "A_A") (pintype "passive"))
      (node (ref "LED42") (pin "A") (pinfunction "A_A") (pintype "passive"))
      (node (ref "LED43") (pin "A") (pinfunction "A_A") (pintype "passive"))
      (node (ref "LED44") (pin "A") (pinfunction "A_A") (pintype "passive"))
      (node (ref "LED45") (pin "A") (pinfunction "A_A") (pintype "passive"))
      (node (ref "LED46") (pin "A") (pinfunction "A_A") (pintype "passive"))
      (node (ref "LED47") (pin "A") (pinfunction "A_A") (pintype "passive"))
      (node (ref "LED48") (pin "A") (pinfunction "A_A") (pintype "passive"))
      (node (ref "Q3") (pin "2") (pinfunction "D_2") (pintype "passive"))
      (node (ref "Q3") (pin "4") (pinfunction "D_4") (pintype "passive"))
    )
    (net (code "34") (name "Net-(LED49-PadA)") (class "Default")
      (node (ref "LED49") (pin "A") (pinfunction "A_A") (pintype "passive"))
      (node (ref "LED50") (pin "A") (pinfunction "A_A") (pintype "passive"))
      (node (ref "LED51") (pin "A") (pinfunction "A_A") (pintype "passive"))
      (node (ref "LED52") (pin "A") (pinfunction "A_A") (pintype "passive"))
      (node (ref "LED53") (pin "A") (pinfunction "A_A") (pintype "passive"))
      (node (ref "LED54") (pin "A") (pinfunction "A_A") (pintype "passive"))
      (node (ref "LED55") (pin "A") (pinfunction "A_A") (pintype "passive"))
      (node (ref "LED56") (pin "A") (pinfunction "A_A") (pintype "passive"))
      (node (ref "LED57") (pin "A") (pinfunction "A_A") (pintype "passive"))
      (node (ref "LED58") (pin "A") (pinfunction "A_A") (pintype "passive"))
      (node (ref "LED59") (pin "A") (pinfunction "A_A") (pintype "passive"))
      (node (ref "LED60") (pin "A") (pinfunction "A_A") (pintype "passive"))
      (node (ref "LED61") (pin "A") (pinfunction "A_A") (pintype "passive"))
      (node (ref "LED62") (pin "A") (pinfunction "A_A") (pintype "passive"))
      (node (ref "LED63") (pin "A") (pinfunction "A_A") (pintype "passive"))
      (node (ref "LED64") (pin "A") (pinfunction "A_A") (pintype "passive"))
      (node (ref "Q4") (pin "2") (pinfunction "D_2") (pintype "passive"))
      (node (ref "Q4") (pin "4") (pinfunction "D_4") (pintype "passive"))
    )
    (net (code "35") (name "Net-(U$2-IREF)") (class "Default")
      (node (ref "R3") (pin "1") (pinfunction "1_1") (pintype "passive"))
      (node (ref "U$2") (pin "27") (pinfunction "IREF_27") (pintype "power_in"))
    )
    (net (code "36") (name "VCC") (class "Default")
      (node (ref "C1") (pin "1") (pinfunction "1_1") (pintype "passive"))
      (node (ref "C2") (pin "1") (pinfunction "1_1") (pintype "passive"))
      (node (ref "C3") (pin "1") (pinfunction "1_1") (pintype "passive"))
      (node (ref "IC2") (pin "10") (pinfunction "SCL_10") (pintype "input"))
      (node (ref "IC2") (pin "16") (pinfunction "VCC_16") (pintype "power_in"))
      (node (ref "JP1") (pin "1") (pinfunction "1_1") (pintype "passive"))
      (node (ref "R2") (pin "2") (pinfunction "2_2") (pintype "passive"))
      (node (ref "U$2") (pin "26") (pinfunction "DCPRG_26") (pintype "input"))
      (node (ref "U$2") (pin "28") (pinfunction "VCC_28") (pintype "power_in"))
    )
    (net (code "37") (name "unconnected-(IC2A-QE-Pad4)") (class "Default")
      (node (ref "IC2") (pin "4") (pinfunction "QE_4") (pintype "tri_state"))
    )
    (net (code "38") (name "unconnected-(IC2A-QF-Pad5)") (class "Default")
      (node (ref "IC2") (pin "5") (pinfunction "QF_5") (pintype "tri_state"))
    )
    (net (code "39") (name "unconnected-(IC2A-QG-Pad6)") (class "Default")
      (node (ref "IC2") (pin "6") (pinfunction "QG_6") (pintype "tri_state"))
    )
    (net (code "40") (name "unconnected-(IC2A-QH*-Pad9)") (class "Default")
      (node (ref "IC2") (pin "9") (pinfunction "QH*_9") (pintype "tri_state"))
    )
    (net (code "41") (name "unconnected-(IC2A-QH-Pad7)") (class "Default")
      (node (ref "IC2") (pin "7") (pinfunction "QH_7") (pintype "tri_state"))
    )
  )
)
